# source_eagle.net
KiCad netlist of a schematic drawn in EAGLE
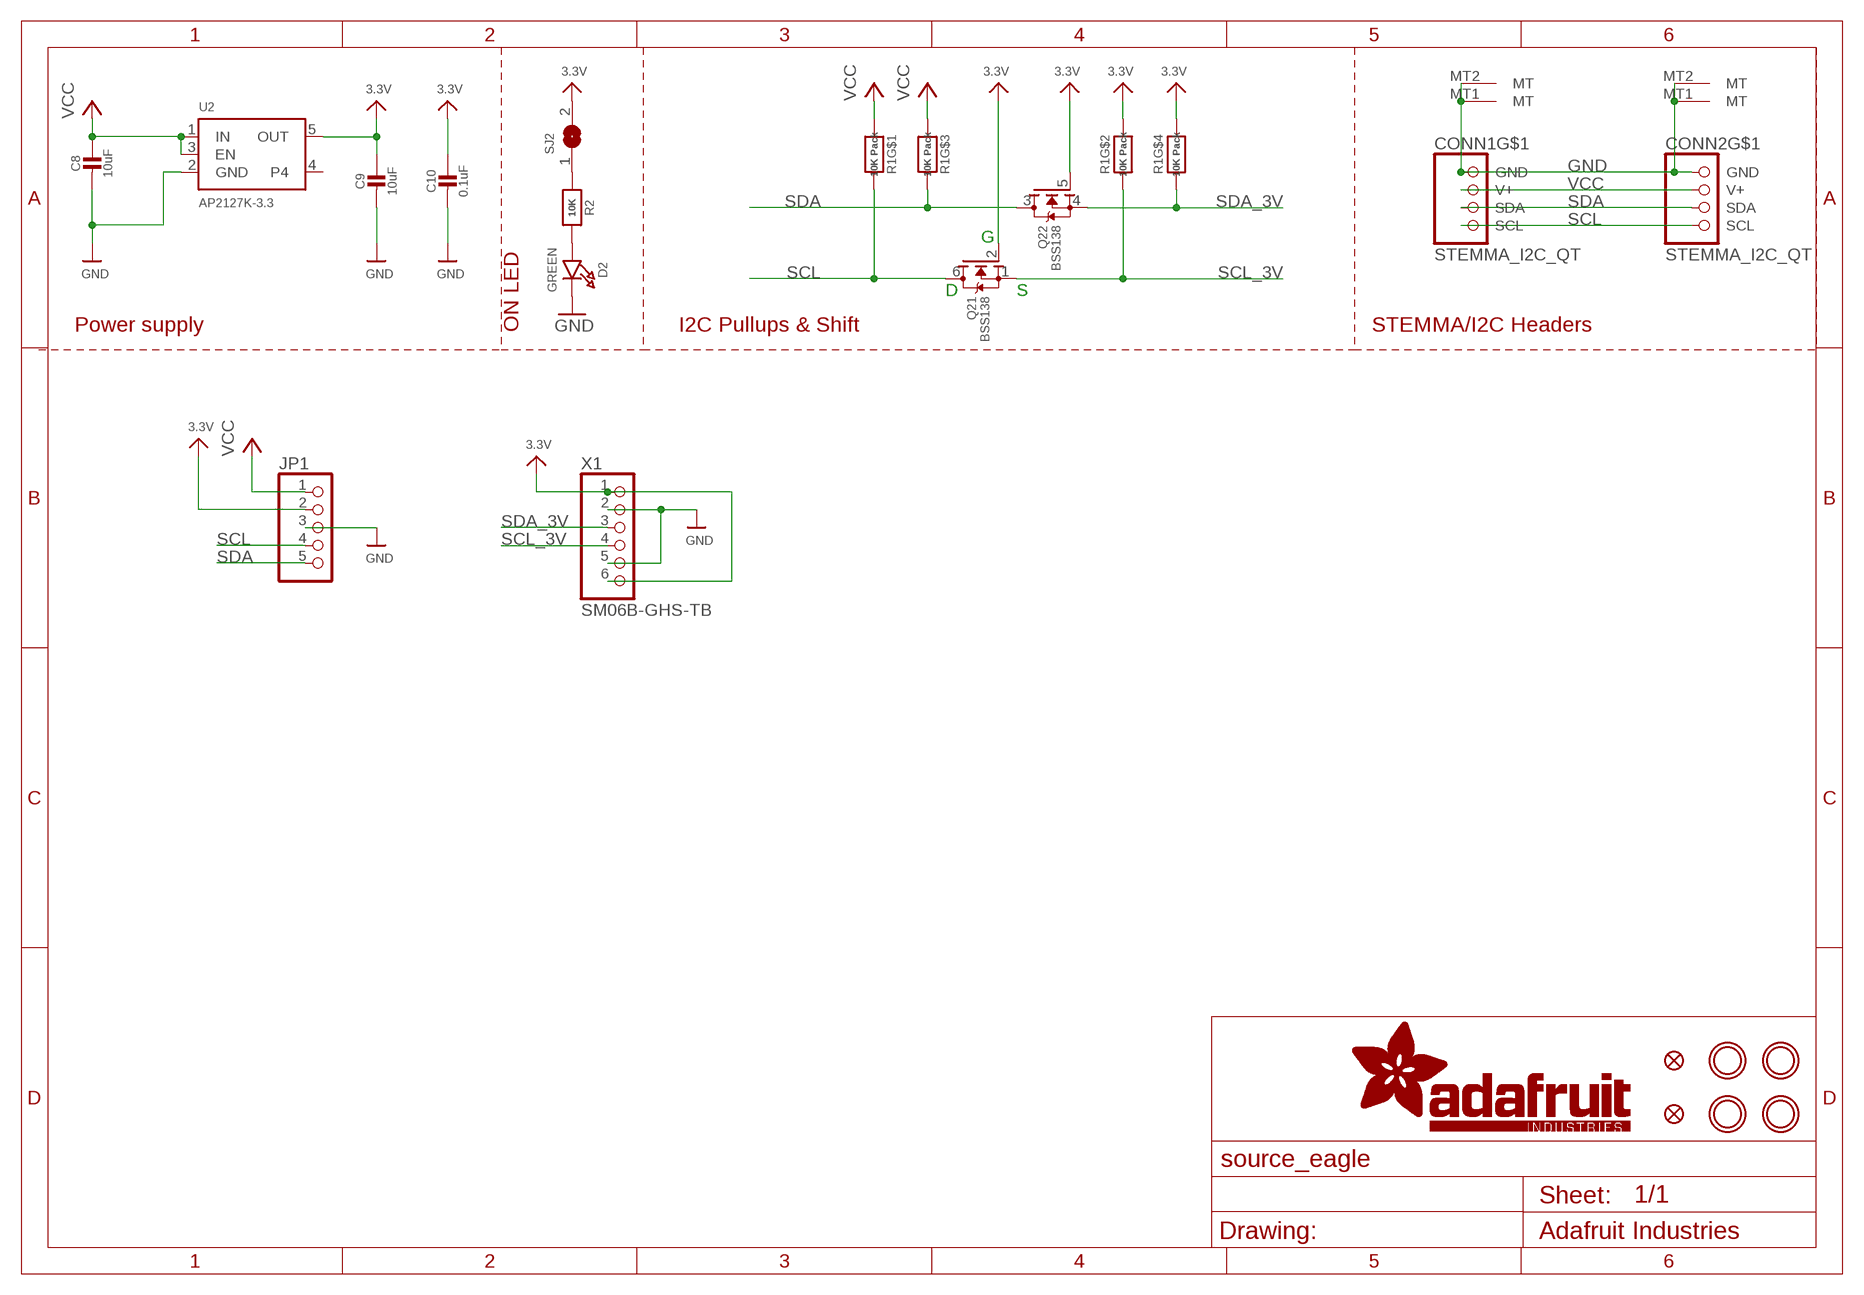
[diagram p0: schematic, sheet 1]

(export (version "E")
  (design (tool "Eeschema 10.0.6"))
  (components
    (comp (ref "C8")
      (value "10uF")
      (footprint "eagle-import:0805-NO")
      (libsource (lib "eagle-import") (part "CAP_CERAMIC0805-NOOUTLINE"))
    )
    (comp (ref "C9")
      (value "10uF")
      (footprint "eagle-import:0805-NO")
      (libsource (lib "eagle-import") (part "CAP_CERAMIC0805-NOOUTLINE"))
    )
    (comp (ref "C10")
      (value "0.1uF")
      (footprint "eagle-import:0603-NO")
      (libsource (lib "eagle-import") (part "CAP_CERAMIC0603_NO"))
    )
    (comp (ref "CONN1")
      (value "STEMMA_I2C_QT")
      (footprint "eagle-import:JST_SH4")
      (libsource (lib "eagle-import") (part "STEMMA_I2C_QT"))
    )
    (comp (ref "CONN2")
      (value "STEMMA_I2C_QT")
      (footprint "eagle-import:JST_SH4")
      (libsource (lib "eagle-import") (part "STEMMA_I2C_QT"))
    )
    (comp (ref "D2")
      (value "GREEN")
      (footprint "eagle-import:CHIPLED_0603_NOOUTLINE")
      (libsource (lib "eagle-import") (part "LED0603_NOOUTLINE"))
    )
    (comp (ref "FID1")
      (value "FIDUCIAL_0.5MM")
      (footprint "eagle-import:FIDUCIAL_0.5MM")
      (libsource (lib "eagle-import") (part "FIDUCIAL_0.5MM"))
    )
    (comp (ref "FID2")
      (value "FIDUCIAL_0.5MM")
      (footprint "eagle-import:FIDUCIAL_0.5MM")
      (libsource (lib "eagle-import") (part "FIDUCIAL_0.5MM"))
    )
    (comp (ref "JP1")
      (value "HEADER-1X570MIL")
      (footprint "eagle-import:1X05_ROUND_70")
      (libsource (lib "eagle-import") (part "HEADER-1X570MIL"))
    )
    (comp (ref "Q2")
      (value "BSS138")
      (footprint "eagle-import:SOT363")
      (libsource (lib "eagle-import") (part "MOSFET-N_DUAL"))
    )
    (comp (ref "R1")
      (value "10K Pack")
      (footprint "eagle-import:RESPACK_4X0603")
      (libsource (lib "eagle-import") (part "RESISTOR_4PACK"))
    )
    (comp (ref "R2")
      (value "10K")
      (footprint "eagle-import:0603-NO")
      (libsource (lib "eagle-import") (part "RESISTOR_0603_NOOUT"))
    )
    (comp (ref "SJ2")
      (value "SOLDERJUMPERCLOSED")
      (footprint "eagle-import:SOLDERJUMPER_CLOSEDWIRE")
      (libsource (lib "eagle-import") (part "SOLDERJUMPERCLOSED"))
    )
    (comp (ref "U$35")
      (value "MOUNTINGHOLE2.5")
      (footprint "eagle-import:MOUNTINGHOLE_2.5_PLATED")
      (libsource (lib "eagle-import") (part "MOUNTINGHOLE2.5"))
    )
    (comp (ref "U$36")
      (value "MOUNTINGHOLE2.5")
      (footprint "eagle-import:MOUNTINGHOLE_2.5_PLATED")
      (libsource (lib "eagle-import") (part "MOUNTINGHOLE2.5"))
    )
    (comp (ref "U$38")
      (value "MOUNTINGHOLE2.5")
      (footprint "eagle-import:MOUNTINGHOLE_2.5_PLATED")
      (libsource (lib "eagle-import") (part "MOUNTINGHOLE2.5"))
    )
    (comp (ref "U$39")
      (value "MOUNTINGHOLE2.5")
      (footprint "eagle-import:MOUNTINGHOLE_2.5_PLATED")
      (libsource (lib "eagle-import") (part "MOUNTINGHOLE2.5"))
    )
    (comp (ref "U2")
      (value "AP2127K-3.3")
      (footprint "eagle-import:SOT23-5")
      (libsource (lib "eagle-import") (part "VREG_SOT23-5"))
    )
    (comp (ref "X1")
      (value "SM06B-GHS-TB")
      (footprint "eagle-import:CONN_SM06B-GHS-TB_JST")
      (libsource (lib "eagle-import") (part "CON_JST_PH_6PIN_SM06S_GHS"))
    )
  )
  (nets
    (net (code "1") (name "/SCL") (class "Default")
      (node (ref "CONN1") (pin "4") (pinfunction "SCL_4") (pintype "passive"))
      (node (ref "CONN2") (pin "4") (pinfunction "SCL_4") (pintype "passive"))
      (node (ref "JP1") (pin "4") (pinfunction "4_4") (pintype "passive"))
      (node (ref "Q2") (pin "6") (pinfunction "D_6") (pintype "bidirectional"))
      (node (ref "R1") (pin "8") (pinfunction "2_8") (pintype "passive"))
    )
    (net (code "2") (name "/SCL_3V") (class "Default")
      (node (ref "Q2") (pin "1") (pinfunction "S_1") (pintype "bidirectional"))
      (node (ref "R1") (pin "7") (pinfunction "2_7") (pintype "passive"))
      (node (ref "X1") (pin "4") (pinfunction "4_4") (pintype "passive"))
    )
    (net (code "3") (name "/SDA") (class "Default")
      (node (ref "CONN1") (pin "3") (pinfunction "SDA_3") (pintype "passive"))
      (node (ref "CONN2") (pin "3") (pinfunction "SDA_3") (pintype "passive"))
      (node (ref "JP1") (pin "5") (pinfunction "5_5") (pintype "passive"))
      (node (ref "Q2") (pin "3") (pinfunction "D_3") (pintype "bidirectional"))
      (node (ref "R1") (pin "6") (pinfunction "2_6") (pintype "passive"))
    )
    (net (code "4") (name "/SDA_3V") (class "Default")
      (node (ref "Q2") (pin "4") (pinfunction "S_4") (pintype "bidirectional"))
      (node (ref "R1") (pin "5") (pinfunction "2_5") (pintype "passive"))
      (node (ref "X1") (pin "3") (pinfunction "3_3") (pintype "passive"))
    )
    (net (code "5") (name "3.3V") (class "Default")
      (node (ref "C10") (pin "1") (pinfunction "1_1") (pintype "passive"))
      (node (ref "C9") (pin "1") (pinfunction "1_1") (pintype "passive"))
      (node (ref "JP1") (pin "2") (pinfunction "2_2") (pintype "passive"))
      (node (ref "Q2") (pin "2") (pinfunction "G_2") (pintype "bidirectional"))
      (node (ref "Q2") (pin "5") (pinfunction "G_5") (pintype "bidirectional"))
      (node (ref "R1") (pin "2") (pinfunction "1_2") (pintype "passive"))
      (node (ref "R1") (pin "4") (pinfunction "1_4") (pintype "passive"))
      (node (ref "SJ2") (pin "2") (pinfunction "2_2") (pintype "passive"))
      (node (ref "U2") (pin "5") (pinfunction "OUT_5") (pintype "power_in"))
      (node (ref "X1") (pin "1") (pinfunction "1_1") (pintype "passive"))
      (node (ref "X1") (pin "6") (pinfunction "6_6") (pintype "passive"))
    )
    (net (code "6") (name "GND") (class "Default")
      (node (ref "C10") (pin "2") (pinfunction "2_2") (pintype "passive"))
      (node (ref "C8") (pin "2") (pinfunction "2_2") (pintype "passive"))
      (node (ref "C9") (pin "2") (pinfunction "2_2") (pintype "passive"))
      (node (ref "CONN1") (pin "1") (pinfunction "GND_1") (pintype "passive"))
      (node (ref "CONN1") (pin "MT1") (pinfunction "MT_MT1") (pintype "bidirectional"))
      (node (ref "CONN1") (pin "MT2") (pinfunction "MT_MT2") (pintype "bidirectional"))
      (node (ref "CONN2") (pin "1") (pinfunction "GND_1") (pintype "passive"))
      (node (ref "CONN2") (pin "MT1") (pinfunction "MT_MT1") (pintype "bidirectional"))
      (node (ref "CONN2") (pin "MT2") (pinfunction "MT_MT2") (pintype "bidirectional"))
      (node (ref "D2") (pin "C") (pinfunction "C_C") (pintype "passive"))
      (node (ref "JP1") (pin "3") (pinfunction "3_3") (pintype "passive"))
      (node (ref "U2") (pin "2") (pinfunction "GND_2") (pintype "power_in"))
      (node (ref "X1") (pin "2") (pinfunction "2_2") (pintype "passive"))
      (node (ref "X1") (pin "5") (pinfunction "5_5") (pintype "passive"))
    )
    (net (code "7") (name "Net-(D2-PadA)") (class "Default")
      (node (ref "D2") (pin "A") (pinfunction "A_A") (pintype "passive"))
      (node (ref "R2") (pin "2") (pinfunction "2_2") (pintype "passive"))
    )
    (net (code "8") (name "Net-(R2-Pad1)") (class "Default")
      (node (ref "R2") (pin "1") (pinfunction "1_1") (pintype "passive"))
      (node (ref "SJ2") (pin "1") (pinfunction "1_1") (pintype "passive"))
    )
    (net (code "9") (name "VCC") (class "Default")
      (node (ref "C8") (pin "1") (pinfunction "1_1") (pintype "passive"))
      (node (ref "CONN1") (pin "2") (pinfunction "V+_2") (pintype "passive"))
      (node (ref "CONN2") (pin "2") (pinfunction "V+_2") (pintype "passive"))
      (node (ref "JP1") (pin "1") (pinfunction "1_1") (pintype "passive"))
      (node (ref "R1") (pin "1") (pinfunction "1_1") (pintype "passive"))
      (node (ref "R1") (pin "3") (pinfunction "1_3") (pintype "passive"))
      (node (ref "U2") (pin "1") (pinfunction "IN_1") (pintype "power_in"))
      (node (ref "U2") (pin "3") (pinfunction "EN_3") (pintype "input"))
    )
    (net (code "10") (name "unconnected-(U2-P4-Pad4)") (class "Default")
      (node (ref "U2") (pin "4") (pinfunction "P4_4") (pintype "bidirectional"))
    )
  )
)
